# bbhTiny85.net
KiCad netlist of a schematic drawn in EAGLE
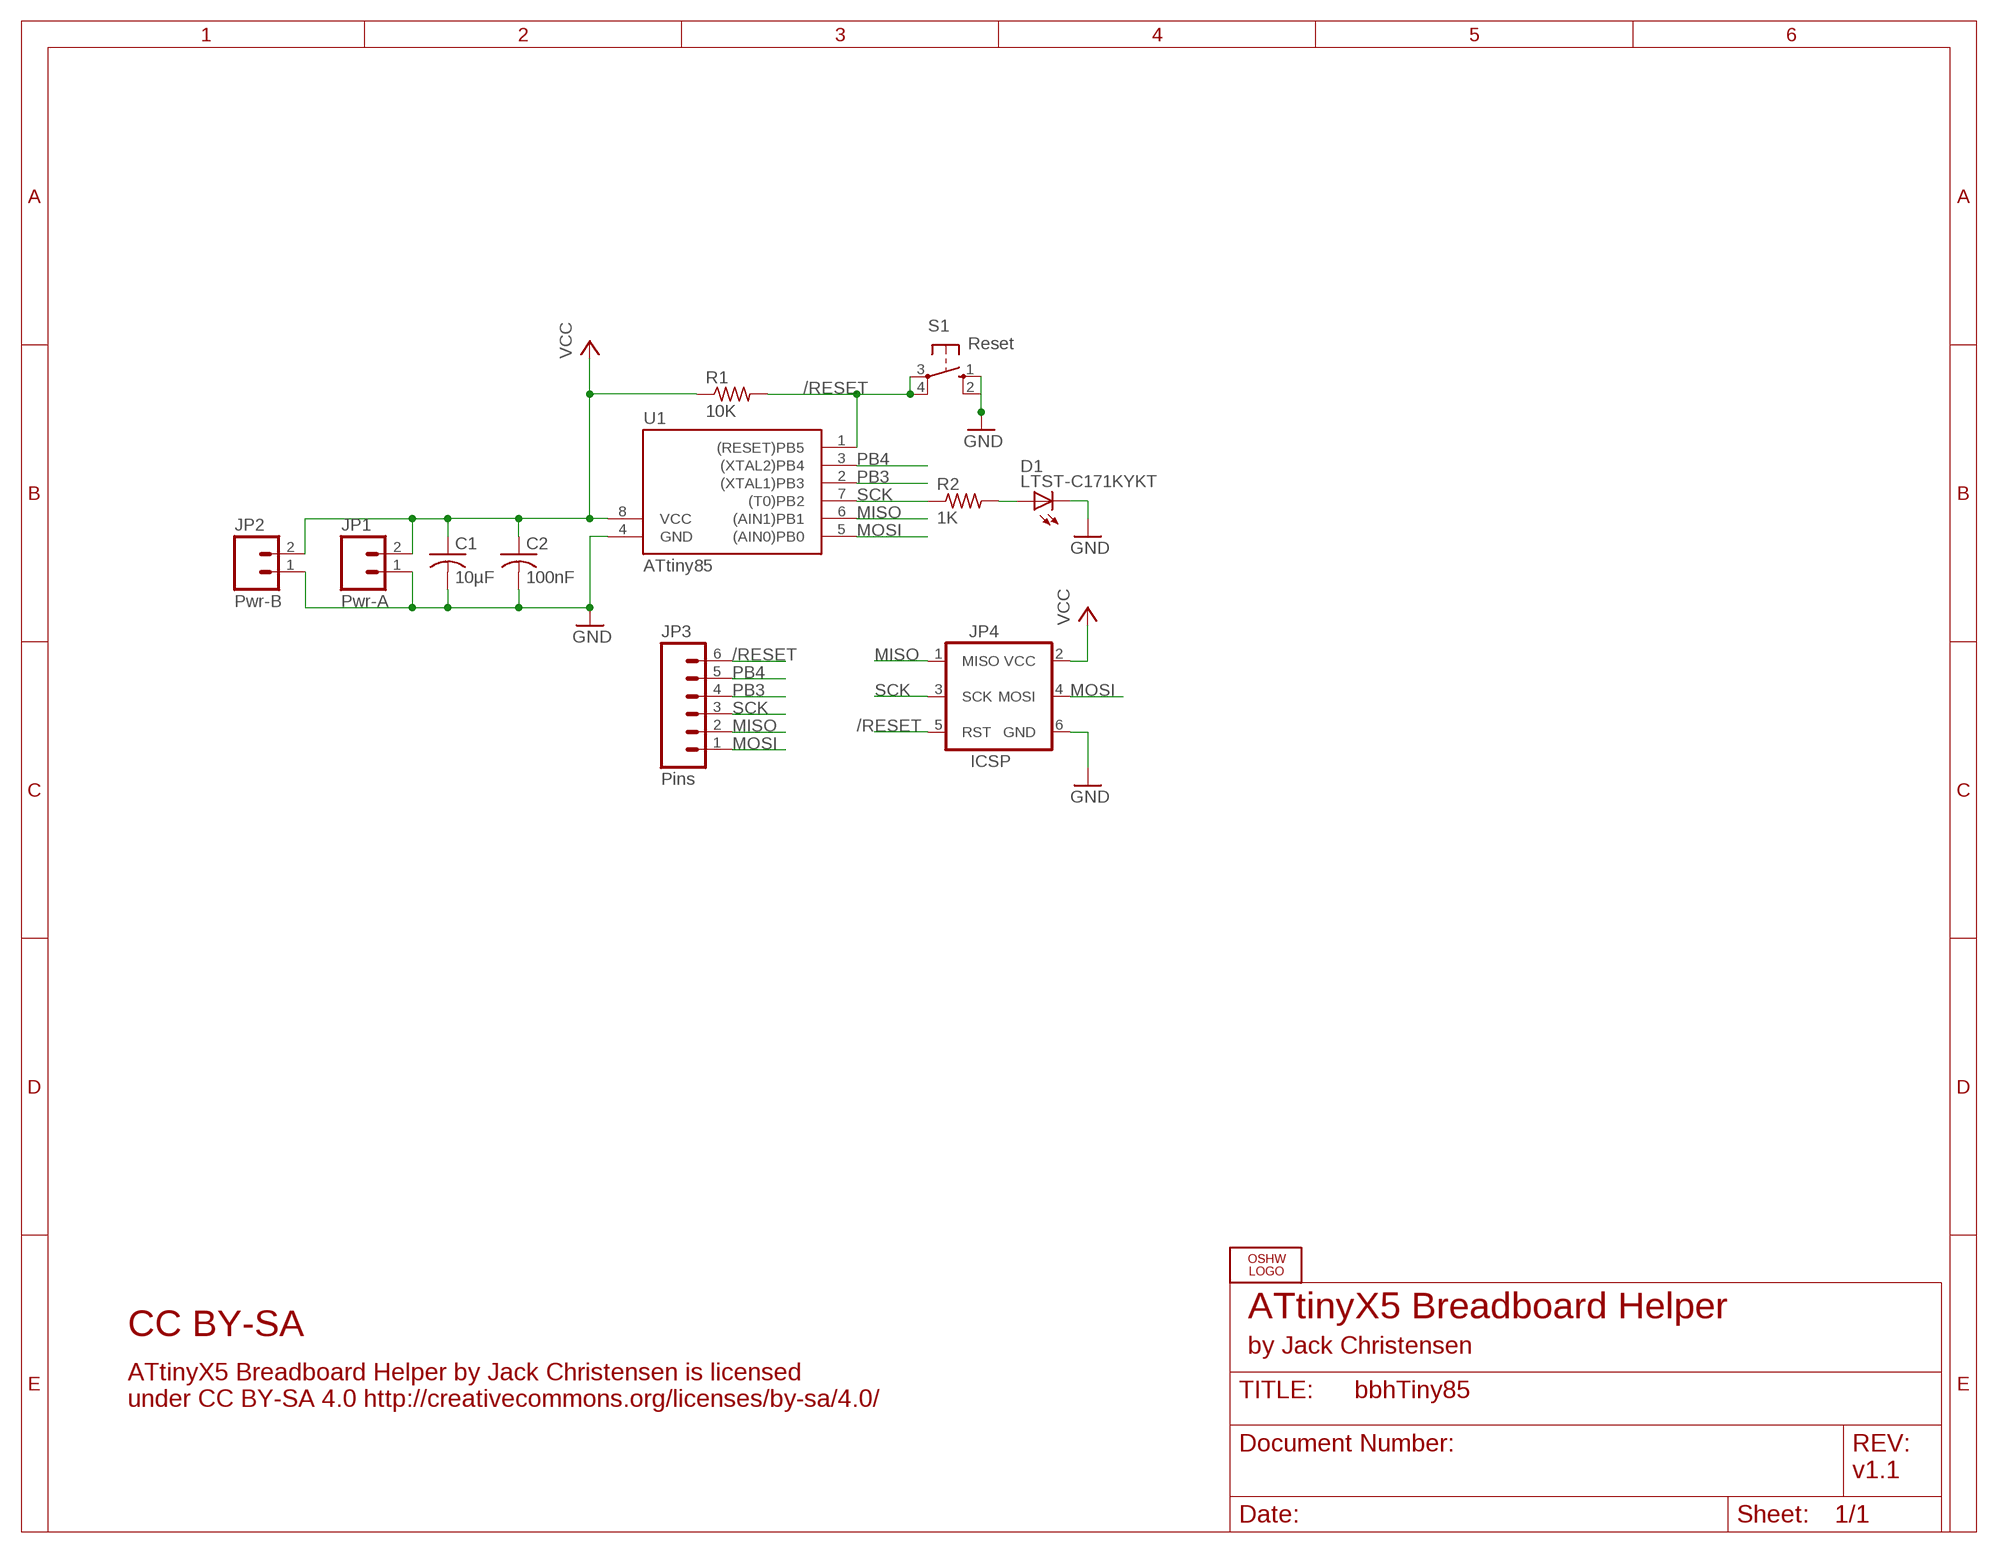
[diagram p0: schematic, sheet 1]

(export (version "E")
  (design (tool "Eeschema 10.0.6"))
  (components
    (comp (ref "C1")
      (value "10µF")
      (footprint "eagle-import:M0805")
      (libsource (lib "eagle-import") (part "C-USM0805"))
    )
    (comp (ref "C2")
      (value "100nF")
      (footprint "eagle-import:M0805")
      (libsource (lib "eagle-import") (part "C-USM0805"))
    )
    (comp (ref "D1")
      (value "LTST-C171KYKT")
      (footprint "eagle-import:D0805A")
      (libsource (lib "eagle-import") (part "LEDD0805A"))
    )
    (comp (ref "JP1")
      (value "Pwr-A")
      (footprint "eagle-import:1X02")
      (libsource (lib "eagle-import") (part "M02PTH"))
    )
    (comp (ref "JP2")
      (value "Pwr-B")
      (footprint "eagle-import:1X02")
      (libsource (lib "eagle-import") (part "M02PTH"))
    )
    (comp (ref "JP3")
      (value "Pins")
      (footprint "eagle-import:1X06")
      (libsource (lib "eagle-import") (part "M06SIP"))
    )
    (comp (ref "JP4")
      (value "ICSP")
      (footprint "eagle-import:2X3_LOCK")
      (libsource (lib "eagle-import") (part "AVR_SPI_PRG_62X3_LOCK"))
    )
    (comp (ref "LOGO1")
      (value "OSHW_LOGO_8MILX0100-NT")
      (footprint "eagle-import:OSHW_8X100_NOTEXT")
      (libsource (lib "eagle-import") (part "OSHW_LOGO_8MILX0100-NT"))
    )
    (comp (ref "R1")
      (value "10K")
      (footprint "eagle-import:M0805")
      (libsource (lib "eagle-import") (part "R-US_M0805"))
    )
    (comp (ref "R2")
      (value "1K")
      (footprint "eagle-import:M0805")
      (libsource (lib "eagle-import") (part "R-US_M0805"))
    )
    (comp (ref "S1")
      (value "Reset")
      (footprint "eagle-import:B3F-10XXOCT")
      (libsource (lib "eagle-import") (part "10-XXOCT"))
    )
    (comp (ref "U1")
      (value "ATtiny85")
      (footprint "eagle-import:DIL08")
      (libsource (lib "eagle-import") (part "TINY10P"))
    )
  )
  (nets
    (net (code "1") (name "/MISO") (class "Default")
      (node (ref "JP3") (pin "2") (pinfunction "2_2") (pintype "passive"))
      (node (ref "JP4") (pin "1") (pinfunction "MISO_1") (pintype "passive"))
      (node (ref "U1") (pin "6") (pinfunction "(AIN1)PB1_6") (pintype "bidirectional"))
    )
    (net (code "2") (name "/MOSI") (class "Default")
      (node (ref "JP3") (pin "1") (pinfunction "1_1") (pintype "passive"))
      (node (ref "JP4") (pin "4") (pinfunction "MOSI_4") (pintype "passive"))
      (node (ref "U1") (pin "5") (pinfunction "(AIN0)PB0_5") (pintype "bidirectional"))
    )
    (net (code "3") (name "/PB3") (class "Default")
      (node (ref "JP3") (pin "4") (pinfunction "4_4") (pintype "passive"))
      (node (ref "U1") (pin "2") (pinfunction "(XTAL1)PB3_2") (pintype "bidirectional"))
    )
    (net (code "4") (name "/PB4") (class "Default")
      (node (ref "JP3") (pin "5") (pinfunction "5_5") (pintype "passive"))
      (node (ref "U1") (pin "3") (pinfunction "(XTAL2)PB4_3") (pintype "bidirectional"))
    )
    (net (code "5") (name "/SCK") (class "Default")
      (node (ref "JP3") (pin "3") (pinfunction "3_3") (pintype "passive"))
      (node (ref "JP4") (pin "3") (pinfunction "SCK_3") (pintype "passive"))
      (node (ref "R2") (pin "1") (pinfunction "1_1") (pintype "passive"))
      (node (ref "U1") (pin "7") (pinfunction "(T0)PB2_7") (pintype "bidirectional"))
    )
    (net (code "6") (name "/{slash}RESET") (class "Default")
      (node (ref "JP3") (pin "6") (pinfunction "6_6") (pintype "passive"))
      (node (ref "JP4") (pin "5") (pinfunction "RST_5") (pintype "passive"))
      (node (ref "R1") (pin "2") (pinfunction "2_2") (pintype "passive"))
      (node (ref "S1") (pin "3") (pinfunction "P_3") (pintype "passive"))
      (node (ref "S1") (pin "4") (pinfunction "P1_4") (pintype "passive"))
      (node (ref "U1") (pin "1") (pinfunction "(RESET)PB5_1") (pintype "bidirectional"))
    )
    (net (code "7") (name "GND") (class "Default")
      (node (ref "C1") (pin "2") (pinfunction "2_2") (pintype "passive"))
      (node (ref "C2") (pin "2") (pinfunction "2_2") (pintype "passive"))
      (node (ref "D1") (pin "K") (pinfunction "C_K") (pintype "passive"))
      (node (ref "JP1") (pin "1") (pinfunction "1_1") (pintype "passive"))
      (node (ref "JP2") (pin "1") (pinfunction "1_1") (pintype "passive"))
      (node (ref "JP4") (pin "6") (pinfunction "GND_6") (pintype "passive"))
      (node (ref "S1") (pin "1") (pinfunction "S_1") (pintype "passive"))
      (node (ref "S1") (pin "2") (pinfunction "S1_2") (pintype "passive"))
      (node (ref "U1") (pin "4") (pinfunction "GND_4") (pintype "power_in"))
    )
    (net (code "8") (name "Net-(D1-PadA)") (class "Default")
      (node (ref "D1") (pin "A") (pinfunction "A_A") (pintype "passive"))
      (node (ref "R2") (pin "2") (pinfunction "2_2") (pintype "passive"))
    )
    (net (code "9") (name "VCC") (class "Default")
      (node (ref "C1") (pin "1") (pinfunction "1_1") (pintype "passive"))
      (node (ref "C2") (pin "1") (pinfunction "1_1") (pintype "passive"))
      (node (ref "JP1") (pin "2") (pinfunction "2_2") (pintype "passive"))
      (node (ref "JP2") (pin "2") (pinfunction "2_2") (pintype "passive"))
      (node (ref "JP4") (pin "2") (pinfunction "VCC_2") (pintype "passive"))
      (node (ref "R1") (pin "1") (pinfunction "1_1") (pintype "passive"))
      (node (ref "U1") (pin "8") (pinfunction "VCC_8") (pintype "power_in"))
    )
  )
)
